# mainboard_transmitter_vf0_1.net
KiCad netlist of a schematic drawn in EAGLE
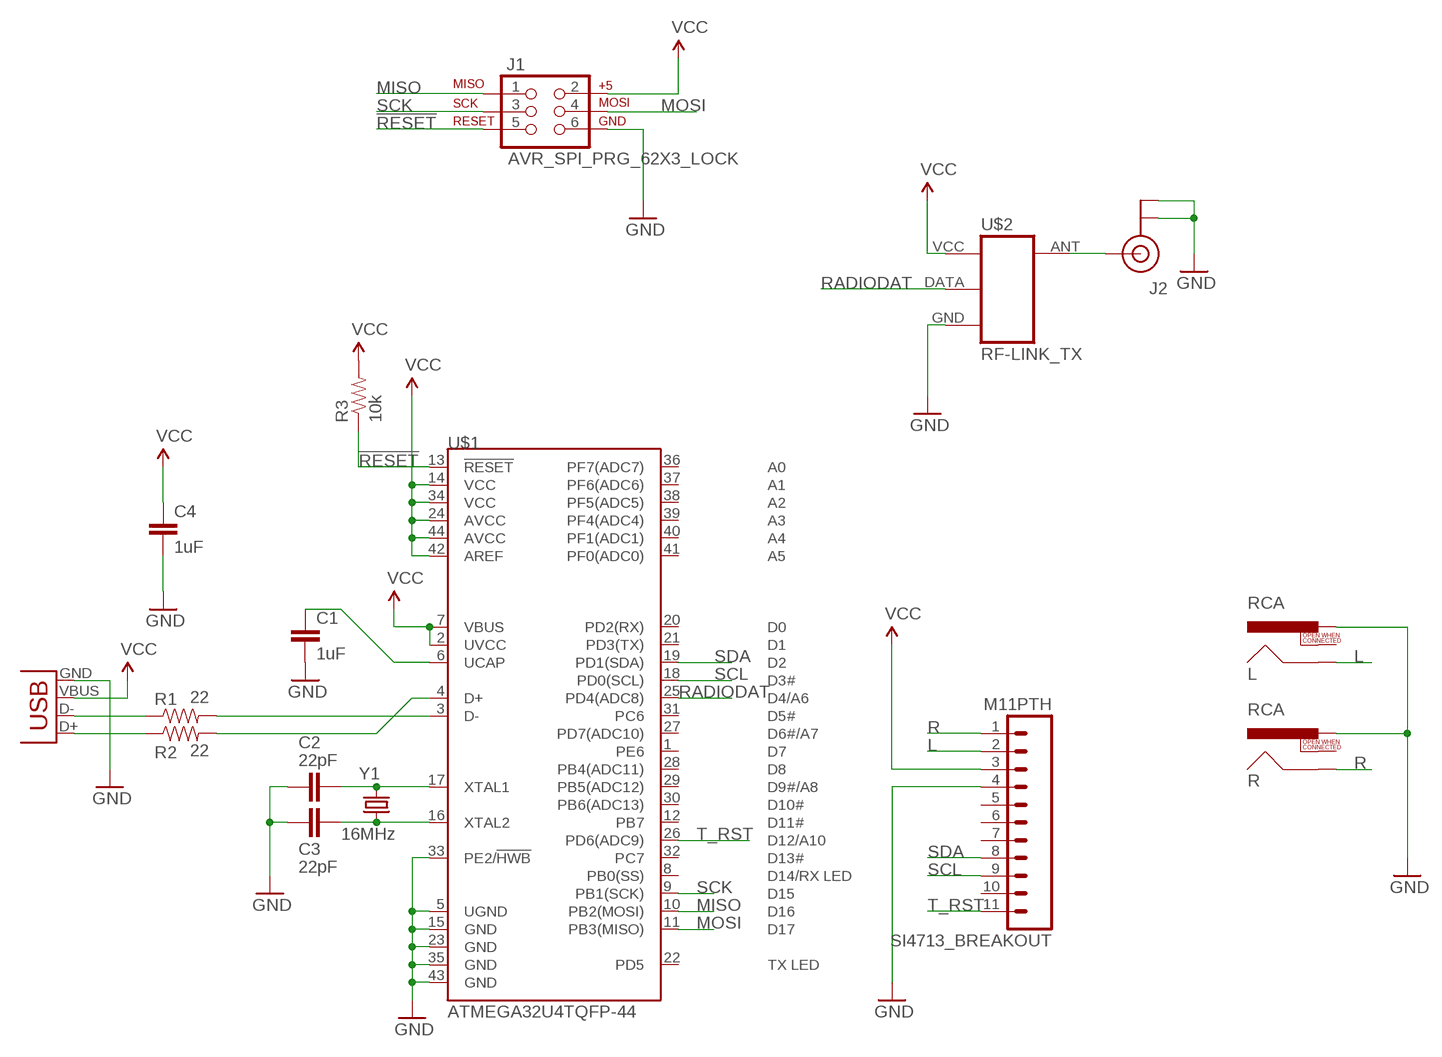
[diagram p0: schematic, sheet 1]

(export (version "E")
  (design (tool "Eeschema 10.0.6"))
  (components
    (comp (ref "C1")
      (value "1uF")
      (footprint "eagle-import:CAP-PTH-SMALL")
      (libsource (lib "eagle-import") (part "CAPPTH"))
    )
    (comp (ref "C2")
      (value "22pF")
      (footprint "eagle-import:CAP-PTH-SMALL")
      (libsource (lib "eagle-import") (part "CAPPTH"))
    )
    (comp (ref "C3")
      (value "22pF")
      (footprint "eagle-import:CAP-PTH-SMALL")
      (libsource (lib "eagle-import") (part "CAPPTH"))
    )
    (comp (ref "C4")
      (value "1uF")
      (footprint "eagle-import:CAP-PTH-SMALL")
      (libsource (lib "eagle-import") (part "CAPPTH"))
    )
    (comp (ref "J1")
      (value "AVR_SPI_PRG_62X3_LOCK")
      (footprint "eagle-import:2X3_LOCK")
      (libsource (lib "eagle-import") (part "AVR_SPI_PRG_62X3_LOCK"))
    )
    (comp (ref "J2")
      (value "U.FL")
      (footprint "eagle-import:U.FL")
      (libsource (lib "eagle-import") (part "U.FL"))
    )
    (comp (ref "JP1")
      (value "USB-B")
      (footprint "eagle-import:USB-B-PTH")
      (libsource (lib "eagle-import") (part "USBPTH"))
    )
    (comp (ref "L")
      (value "RCA")
      (footprint "eagle-import:RCA")
      (libsource (lib "eagle-import") (part "RCA"))
    )
    (comp (ref "R")
      (value "RCA")
      (footprint "eagle-import:RCA")
      (libsource (lib "eagle-import") (part "RCA"))
    )
    (comp (ref "R1")
      (value "22")
      (footprint "eagle-import:AXIAL-0.1")
      (libsource (lib "eagle-import") (part "RESISTORPTH-1/4W-VERT"))
    )
    (comp (ref "R2")
      (value "22")
      (footprint "eagle-import:AXIAL-0.1")
      (libsource (lib "eagle-import") (part "RESISTORPTH-1/4W-VERT"))
    )
    (comp (ref "R3")
      (value "10k")
      (footprint "eagle-import:AXIAL-0.1")
      (libsource (lib "eagle-import") (part "10KOHM-1/4W5%(PTH)VERT"))
    )
    (comp (ref "SI4713_BREAKOUT")
      (value "M11PTH")
      (footprint "eagle-import:1X11")
      (libsource (lib "eagle-import") (part "M11PTH"))
    )
    (comp (ref "U$1")
      (value "ATMEGA32U4TQFP-44")
      (footprint "eagle-import:TQFP44")
      (libsource (lib "eagle-import") (part "ATMEGA32U4TQFP-44"))
    )
    (comp (ref "U$2")
      (value "RF-LINK_TX")
      (footprint "eagle-import:RF-LINK_TX")
      (libsource (lib "eagle-import") (part "RF-LINK_TX"))
    )
    (comp (ref "Y1")
      (value "16MHz")
      (footprint "eagle-import:HC49US")
      (libsource (lib "eagle-import") (part "CRYSTALHC49US"))
    )
  )
  (nets
    (net (code "1") (name "/L") (class "Default")
      (node (ref "L") (pin "SHELL") (pinfunction "SHELL_SHELL") (pintype "bidirectional"))
      (node (ref "SI4713_BREAKOUT") (pin "2") (pinfunction "2_2") (pintype "passive"))
    )
    (net (code "2") (name "/MISO") (class "Default")
      (node (ref "J1") (pin "1") (pinfunction "1_1") (pintype "passive"))
      (node (ref "U$1") (pin "10") (pinfunction "PB2(MOSI)_10") (pintype "bidirectional"))
    )
    (net (code "3") (name "/MOSI") (class "Default")
      (node (ref "J1") (pin "4") (pinfunction "4_4") (pintype "passive"))
      (node (ref "U$1") (pin "11") (pinfunction "PB3(MISO)_11") (pintype "bidirectional"))
    )
    (net (code "4") (name "/R") (class "Default")
      (node (ref "R") (pin "SHELL") (pinfunction "SHELL_SHELL") (pintype "bidirectional"))
      (node (ref "SI4713_BREAKOUT") (pin "1") (pinfunction "1_1") (pintype "passive"))
    )
    (net (code "5") (name "/RADIODAT") (class "Default")
      (node (ref "U$1") (pin "25") (pinfunction "PD4(ADC8)_25") (pintype "bidirectional"))
      (node (ref "U$2") (pin "DATA") (pinfunction "DATA_DATA") (pintype "input"))
    )
    (net (code "6") (name "/SCK") (class "Default")
      (node (ref "J1") (pin "3") (pinfunction "3_3") (pintype "passive"))
      (node (ref "U$1") (pin "9") (pinfunction "PB1(SCK)_9") (pintype "bidirectional"))
    )
    (net (code "7") (name "/SCL") (class "Default")
      (node (ref "SI4713_BREAKOUT") (pin "9") (pinfunction "9_9") (pintype "passive"))
      (node (ref "U$1") (pin "18") (pinfunction "PD0(SCL)_18") (pintype "bidirectional"))
    )
    (net (code "8") (name "/SDA") (class "Default")
      (node (ref "SI4713_BREAKOUT") (pin "8") (pinfunction "8_8") (pintype "passive"))
      (node (ref "U$1") (pin "19") (pinfunction "PD1(SDA)_19") (pintype "bidirectional"))
    )
    (net (code "9") (name "/T_RST") (class "Default")
      (node (ref "SI4713_BREAKOUT") (pin "11") (pinfunction "11_11") (pintype "passive"))
      (node (ref "U$1") (pin "26") (pinfunction "PD6(ADC9)_26") (pintype "bidirectional"))
    )
    (net (code "10") (name "/~{RESET}") (class "Default")
      (node (ref "J1") (pin "5") (pinfunction "5_5") (pintype "passive"))
      (node (ref "R3") (pin "P$1") (pinfunction "1_P$1") (pintype "passive"))
      (node (ref "U$1") (pin "13") (pinfunction "~{RESET}_13") (pintype "bidirectional"))
    )
    (net (code "11") (name "GND") (class "Default")
      (node (ref "C1") (pin "2") (pinfunction "2_2") (pintype "passive"))
      (node (ref "C2") (pin "1") (pinfunction "1_1") (pintype "passive"))
      (node (ref "C3") (pin "1") (pinfunction "1_1") (pintype "passive"))
      (node (ref "C4") (pin "2") (pinfunction "2_2") (pintype "passive"))
      (node (ref "J1") (pin "6") (pinfunction "6_6") (pintype "passive"))
      (node (ref "J2") (pin "P$1") (pinfunction "GND_P$1") (pintype "bidirectional"))
      (node (ref "J2") (pin "P$2") (pinfunction "GND_P$2") (pintype "bidirectional"))
      (node (ref "JP1") (pin "GND") (pinfunction "GND_GND") (pintype "bidirectional"))
      (node (ref "L") (pin "PIN") (pinfunction "PIN_PIN") (pintype "bidirectional"))
      (node (ref "R") (pin "PIN") (pinfunction "PIN_PIN") (pintype "bidirectional"))
      (node (ref "SI4713_BREAKOUT") (pin "4") (pinfunction "4_4") (pintype "passive"))
      (node (ref "U$1") (pin "15") (pinfunction "GND_15") (pintype "bidirectional"))
      (node (ref "U$1") (pin "23") (pinfunction "GND_23") (pintype "bidirectional"))
      (node (ref "U$1") (pin "33") (pinfunction "PE2/~{HWB}_33") (pintype "bidirectional"))
      (node (ref "U$1") (pin "35") (pinfunction "GND_35") (pintype "bidirectional"))
      (node (ref "U$1") (pin "43") (pinfunction "GND_43") (pintype "bidirectional"))
      (node (ref "U$1") (pin "5") (pinfunction "UGND_5") (pintype "bidirectional"))
      (node (ref "U$2") (pin "GND") (pinfunction "GND_GND") (pintype "power_in"))
    )
    (net (code "12") (name "Net-(J2-SIGNAL)") (class "Default")
      (node (ref "J2") (pin "P$3") (pinfunction "SIGNAL_P$3") (pintype "bidirectional"))
      (node (ref "U$2") (pin "ANT") (pinfunction "ANT_ANT") (pintype "passive"))
    )
    (net (code "13") (name "Net-(R1-1)") (class "Default")
      (node (ref "JP1") (pin "D-") (pinfunction "D-_D-") (pintype "bidirectional"))
      (node (ref "R1") (pin "P$1") (pinfunction "1_P$1") (pintype "passive"))
    )
    (net (code "14") (name "Net-(R1-2)") (class "Default")
      (node (ref "R1") (pin "P$2") (pinfunction "2_P$2") (pintype "passive"))
      (node (ref "U$1") (pin "3") (pinfunction "D-_3") (pintype "bidirectional"))
    )
    (net (code "15") (name "Net-(R2-1)") (class "Default")
      (node (ref "JP1") (pin "D+") (pinfunction "D+_D+") (pintype "bidirectional"))
      (node (ref "R2") (pin "P$1") (pinfunction "1_P$1") (pintype "passive"))
    )
    (net (code "16") (name "Net-(R2-2)") (class "Default")
      (node (ref "R2") (pin "P$2") (pinfunction "2_P$2") (pintype "passive"))
      (node (ref "U$1") (pin "4") (pinfunction "D+_4") (pintype "bidirectional"))
    )
    (net (code "17") (name "Net-(U$1-UCAP)") (class "Default")
      (node (ref "C1") (pin "1") (pinfunction "1_1") (pintype "passive"))
      (node (ref "U$1") (pin "6") (pinfunction "UCAP_6") (pintype "bidirectional"))
    )
    (net (code "18") (name "Net-(U$1-XTAL1)") (class "Default")
      (node (ref "C2") (pin "2") (pinfunction "2_2") (pintype "passive"))
      (node (ref "U$1") (pin "17") (pinfunction "XTAL1_17") (pintype "bidirectional"))
      (node (ref "Y1") (pin "2") (pinfunction "2_2") (pintype "passive"))
    )
    (net (code "19") (name "Net-(U$1-XTAL2)") (class "Default")
      (node (ref "C3") (pin "2") (pinfunction "2_2") (pintype "passive"))
      (node (ref "U$1") (pin "16") (pinfunction "XTAL2_16") (pintype "bidirectional"))
      (node (ref "Y1") (pin "1") (pinfunction "1_1") (pintype "passive"))
    )
    (net (code "20") (name "VCC") (class "Default")
      (node (ref "C4") (pin "1") (pinfunction "1_1") (pintype "passive"))
      (node (ref "J1") (pin "2") (pinfunction "2_2") (pintype "passive"))
      (node (ref "JP1") (pin "VBUS") (pinfunction "VBUS_VBUS") (pintype "bidirectional"))
      (node (ref "R3") (pin "P$2") (pinfunction "2_P$2") (pintype "passive"))
      (node (ref "SI4713_BREAKOUT") (pin "3") (pinfunction "3_3") (pintype "passive"))
      (node (ref "U$1") (pin "14") (pinfunction "VCC_14") (pintype "bidirectional"))
      (node (ref "U$1") (pin "2") (pinfunction "UVCC_2") (pintype "bidirectional"))
      (node (ref "U$1") (pin "24") (pinfunction "AVCC_24") (pintype "bidirectional"))
      (node (ref "U$1") (pin "34") (pinfunction "VCC_34") (pintype "bidirectional"))
      (node (ref "U$1") (pin "42") (pinfunction "AREF_42") (pintype "bidirectional"))
      (node (ref "U$1") (pin "44") (pinfunction "AVCC_44") (pintype "bidirectional"))
      (node (ref "U$1") (pin "7") (pinfunction "VBUS_7") (pintype "bidirectional"))
      (node (ref "U$2") (pin "VCC") (pinfunction "+5V_VCC") (pintype "power_in"))
    )
    (net (code "21") (name "unconnected-(L-PadSWITCH)") (class "Default")
      (node (ref "L") (pin "SWITCH") (pinfunction "SWITCH_SWITCH") (pintype "bidirectional"))
    )
    (net (code "22") (name "unconnected-(R-PadSWITCH)") (class "Default")
      (node (ref "R") (pin "SWITCH") (pinfunction "SWITCH_SWITCH") (pintype "bidirectional"))
    )
    (net (code "23") (name "unconnected-(SI4713_BREAKOUT-Pad5)") (class "Default")
      (node (ref "SI4713_BREAKOUT") (pin "5") (pinfunction "5_5") (pintype "passive"))
    )
    (net (code "24") (name "unconnected-(SI4713_BREAKOUT-Pad6)") (class "Default")
      (node (ref "SI4713_BREAKOUT") (pin "6") (pinfunction "6_6") (pintype "passive"))
    )
    (net (code "25") (name "unconnected-(SI4713_BREAKOUT-Pad7)") (class "Default")
      (node (ref "SI4713_BREAKOUT") (pin "7") (pinfunction "7_7") (pintype "passive"))
    )
    (net (code "26") (name "unconnected-(SI4713_BREAKOUT-Pad10)") (class "Default")
      (node (ref "SI4713_BREAKOUT") (pin "10") (pinfunction "10_10") (pintype "passive"))
    )
    (net (code "27") (name "unconnected-(U$1-PB0(SS)-Pad8)") (class "Default")
      (node (ref "U$1") (pin "8") (pinfunction "PB0(SS)_8") (pintype "bidirectional"))
    )
    (net (code "28") (name "unconnected-(U$1-PB4(ADC11)-Pad28)") (class "Default")
      (node (ref "U$1") (pin "28") (pinfunction "PB4(ADC11)_28") (pintype "bidirectional"))
    )
    (net (code "29") (name "unconnected-(U$1-PB5(ADC12)-Pad29)") (class "Default")
      (node (ref "U$1") (pin "29") (pinfunction "PB5(ADC12)_29") (pintype "bidirectional"))
    )
    (net (code "30") (name "unconnected-(U$1-PB6(ADC13)-Pad30)") (class "Default")
      (node (ref "U$1") (pin "30") (pinfunction "PB6(ADC13)_30") (pintype "bidirectional"))
    )
    (net (code "31") (name "unconnected-(U$1-PB7-Pad12)") (class "Default")
      (node (ref "U$1") (pin "12") (pinfunction "PB7_12") (pintype "bidirectional"))
    )
    (net (code "32") (name "unconnected-(U$1-PC6-Pad31)") (class "Default")
      (node (ref "U$1") (pin "31") (pinfunction "PC6_31") (pintype "bidirectional"))
    )
    (net (code "33") (name "unconnected-(U$1-PC7-Pad32)") (class "Default")
      (node (ref "U$1") (pin "32") (pinfunction "PC7_32") (pintype "bidirectional"))
    )
    (net (code "34") (name "unconnected-(U$1-PD2(RX)-Pad20)") (class "Default")
      (node (ref "U$1") (pin "20") (pinfunction "PD2(RX)_20") (pintype "bidirectional"))
    )
    (net (code "35") (name "unconnected-(U$1-PD3(TX)-Pad21)") (class "Default")
      (node (ref "U$1") (pin "21") (pinfunction "PD3(TX)_21") (pintype "bidirectional"))
    )
    (net (code "36") (name "unconnected-(U$1-PD5-Pad22)") (class "Default")
      (node (ref "U$1") (pin "22") (pinfunction "PD5_22") (pintype "bidirectional"))
    )
    (net (code "37") (name "unconnected-(U$1-PD7(ADC10)-Pad27)") (class "Default")
      (node (ref "U$1") (pin "27") (pinfunction "PD7(ADC10)_27") (pintype "bidirectional"))
    )
    (net (code "38") (name "unconnected-(U$1-PE6-Pad1)") (class "Default")
      (node (ref "U$1") (pin "1") (pinfunction "PE6_1") (pintype "bidirectional"))
    )
    (net (code "39") (name "unconnected-(U$1-PF0(ADC0)-Pad41)") (class "Default")
      (node (ref "U$1") (pin "41") (pinfunction "PF0(ADC0)_41") (pintype "bidirectional"))
    )
    (net (code "40") (name "unconnected-(U$1-PF1(ADC1)-Pad40)") (class "Default")
      (node (ref "U$1") (pin "40") (pinfunction "PF1(ADC1)_40") (pintype "bidirectional"))
    )
    (net (code "41") (name "unconnected-(U$1-PF4(ADC4)-Pad39)") (class "Default")
      (node (ref "U$1") (pin "39") (pinfunction "PF4(ADC4)_39") (pintype "bidirectional"))
    )
    (net (code "42") (name "unconnected-(U$1-PF5(ADC5)-Pad38)") (class "Default")
      (node (ref "U$1") (pin "38") (pinfunction "PF5(ADC5)_38") (pintype "bidirectional"))
    )
    (net (code "43") (name "unconnected-(U$1-PF6(ADC6)-Pad37)") (class "Default")
      (node (ref "U$1") (pin "37") (pinfunction "PF6(ADC6)_37") (pintype "bidirectional"))
    )
    (net (code "44") (name "unconnected-(U$1-PF7(ADC7)-Pad36)") (class "Default")
      (node (ref "U$1") (pin "36") (pinfunction "PF7(ADC7)_36") (pintype "bidirectional"))
    )
  )
)
